# airPi_Controller.net
KiCad netlist of a schematic drawn in Altium Designer
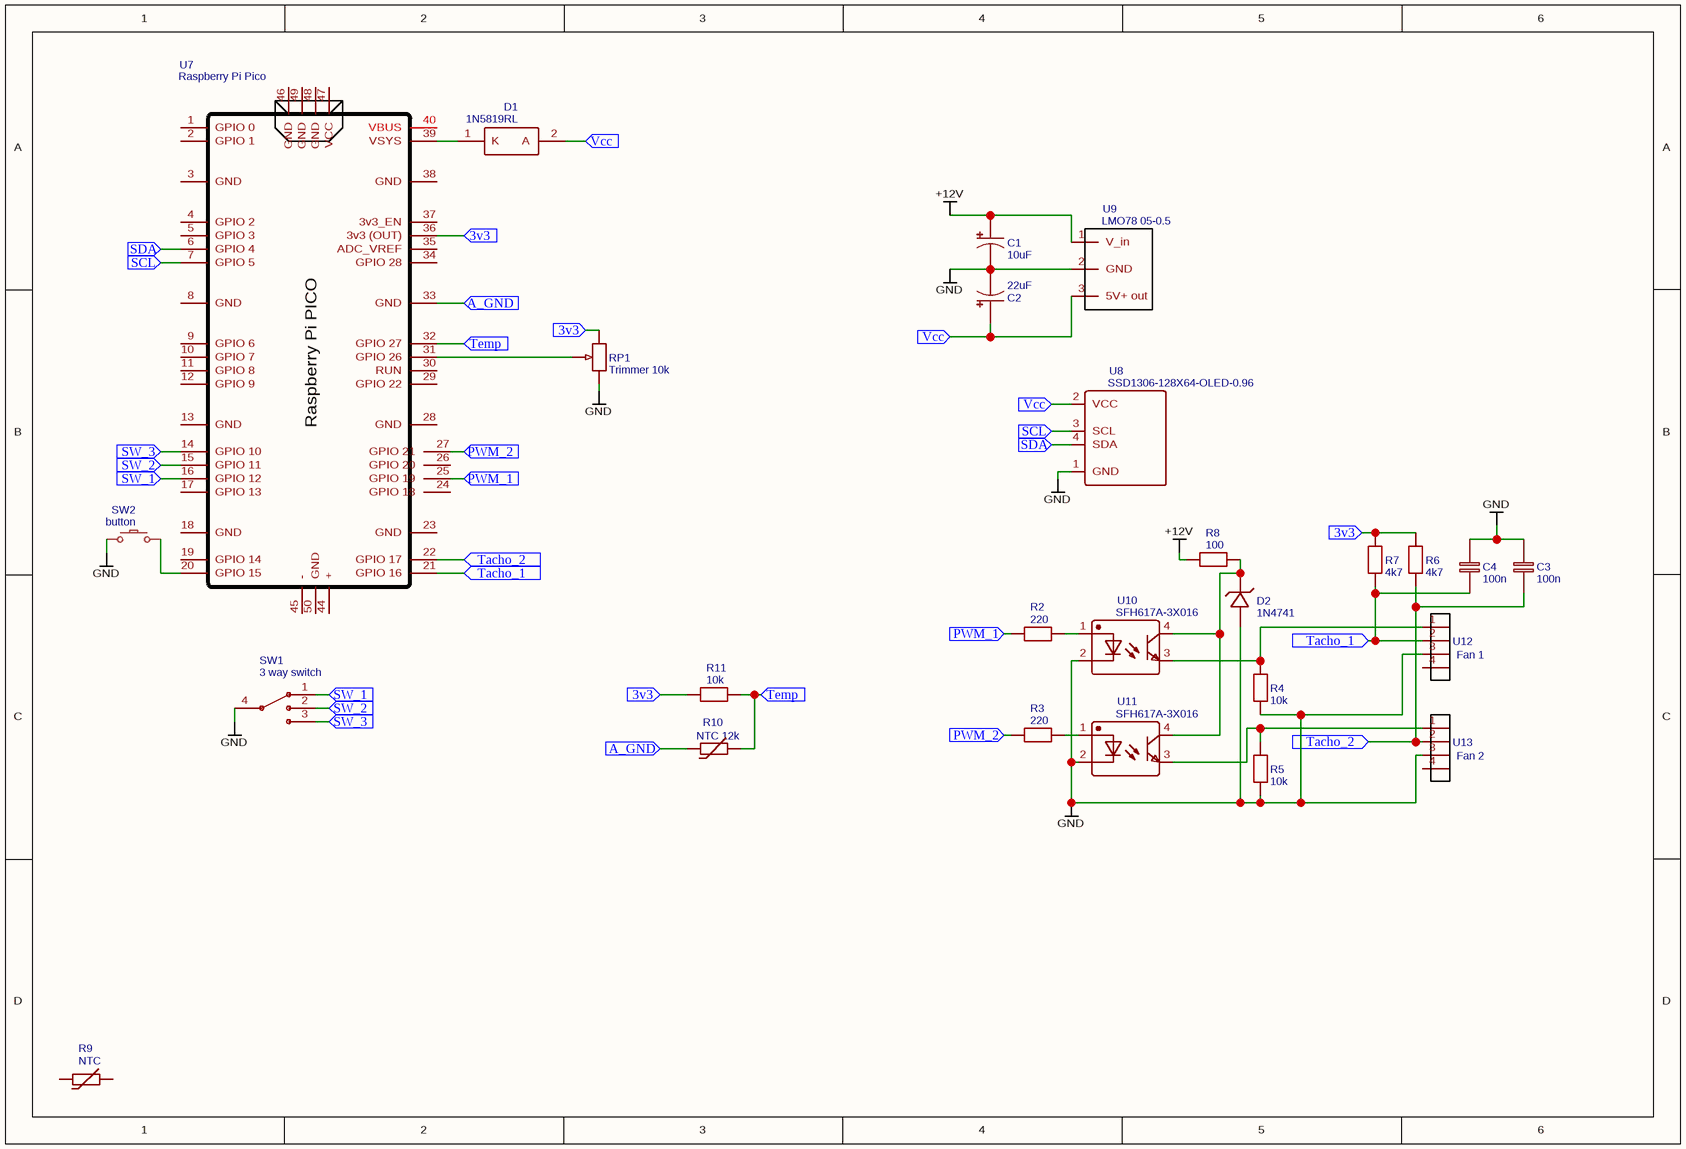
[diagram p0: airPi_Controller.schdoc]

(export (version "E")
  (design (tool "Eeschema 10.0.6"))
  (components
    (comp (ref "C1")
      (value "10uF")
      (fields (field (name "CONTRIBUTOR") "hafiz_8030"))
      (libsource (lib "altium-import") (part "root_0_10uF_"))
    )
    (comp (ref "C2")
      (value "22uF")
      (fields (field (name "CONTRIBUTOR") "hafiz_8030"))
      (libsource (lib "altium-import") (part "root_0_22uF_"))
    )
    (comp (ref "C3")
      (value "100n")
      (fields (field (name "CONTRIBUTOR") "LCEDA_Lib"))
      (libsource (lib "altium-import") (part "root_1_100n_"))
    )
    (comp (ref "C4")
      (value "100n")
      (fields (field (name "CONTRIBUTOR") "LCEDA_Lib"))
      (libsource (lib "altium-import") (part "root_1_100n_"))
    )
    (comp (ref "D1")
      (value "1N5819RL")
      (description "Rectifier, 2-Pin Axial_Lead, Pb-Free, Tape and Reel")
      (libsource (lib "altium-import") (part "root_0_1N5819RL_"))
    )
    (comp (ref "D2")
      (value "1N4741")
      (fields
        (field (name "MANUFACTURER") "onsemi(安森美)")
        (field (name "MANUFACTURER PART") "1N4741A")
        (field (name "CONTRIBUTOR") "LCSC")
      )
      (libsource (lib "altium-import") (part "root_3_1N4741_"))
    )
    (comp (ref "R2")
      (value "220")
      (fields (field (name "CONTRIBUTOR") "LCEDA_Lib"))
      (libsource (lib "altium-import") (part "root_0_220_"))
    )
    (comp (ref "R3")
      (value "220")
      (fields (field (name "CONTRIBUTOR") "LCEDA_Lib"))
      (libsource (lib "altium-import") (part "root_0_220_"))
    )
    (comp (ref "R4")
      (value "10k")
      (fields (field (name "CONTRIBUTOR") "LCEDA_Lib"))
      (libsource (lib "altium-import") (part "root_1_10k_"))
    )
    (comp (ref "R5")
      (value "10k")
      (fields (field (name "CONTRIBUTOR") "LCEDA_Lib"))
      (libsource (lib "altium-import") (part "root_1_10k_"))
    )
    (comp (ref "R6")
      (value "4k7")
      (fields (field (name "CONTRIBUTOR") "LCEDA_Lib"))
      (libsource (lib "altium-import") (part "root_1_4k7_"))
    )
    (comp (ref "R7")
      (value "4k7")
      (fields (field (name "CONTRIBUTOR") "LCEDA_Lib"))
      (libsource (lib "altium-import") (part "root_1_4k7_"))
    )
    (comp (ref "R8")
      (value "100")
      (fields (field (name "CONTRIBUTOR") "LCEDA_Lib"))
      (libsource (lib "altium-import") (part "root_2_100_"))
    )
    (comp (ref "R9")
      (value "NTC")
      (fields (field (name "MANUFACTURER") "RUILON(瑞隆源)") (field (name "MANUFACTURER PART") "NTC 5D-9(弯脚)"))
      (libsource (lib "altium-import") (part "root_0_NTC_"))
    )
    (comp (ref "R10")
      (value "NTC 12k")
      (fields (field (name "MANUFACTURER") "RUILON(瑞隆源)") (field (name "MANUFACTURER PART") "NTC 5D-9(弯脚)"))
      (libsource (lib "altium-import") (part "root_0_NTC 12k_"))
    )
    (comp (ref "R11")
      (value "10k")
      (fields (field (name "CONTRIBUTOR") "LCEDA_Lib"))
      (libsource (lib "altium-import") (part "root_0_10k_"))
    )
    (comp (ref "RP1")
      (value "Trimmer 10k")
      (fields (field (name "CONTRIBUTOR") "LCEDA_Lib"))
      (libsource (lib "altium-import") (part "root_1_Trimmer 10k_"))
    )
    (comp (ref "SW1")
      (value "3 way switch")
      (fields
        (field (name "MANUFACTURER") "ReliaPro")
        (field (name "MANUFACTURER PART") "MSK-11027 Toggle Switches")
        (field (name "CONTRIBUTOR") "ClivePCBDesign")
      )
      (libsource (lib "altium-import") (part "root_0_3 way switch_"))
    )
    (comp (ref "SW2")
      (value "button")
      (fields (field (name "CONTRIBUTOR") "laura.puyet1"))
      (libsource (lib "altium-import") (part "root_0_button_"))
    )
    (comp (ref "U7")
      (value "Raspberry Pi Pico")
      (fields (field (name "CONTRIBUTOR") "grawik"))
      (libsource (lib "altium-import") (part "root_0_Raspberry Pi Pico_"))
    )
    (comp (ref "U8")
      (value "SSD1306-128X64-OLED-0.96")
      (fields (field (name "CONTRIBUTOR") "Think Service"))
      (libsource (lib "altium-import") (part "root_0_SSD1306-128X64-OLED-0.96_"))
    )
    (comp (ref "U9")
      (value "LMO78 05-0.5")
      (fields (field (name "CONTRIBUTOR") "Martin Heiter"))
      (libsource (lib "altium-import") (part "root_3_LMO78 05-0.5_"))
    )
    (comp (ref "U10")
      (value "SFH617A-3X016")
      (fields (field (name "MANUFACTURER") "VISHAY(威世)") (field (name "CONTRIBUTOR") "lcsc"))
      (libsource (lib "altium-import") (part "root_0_SFH617A-3X016_"))
    )
    (comp (ref "U11")
      (value "SFH617A-3X016")
      (fields (field (name "MANUFACTURER") "VISHAY(威世)") (field (name "CONTRIBUTOR") "lcsc"))
      (libsource (lib "altium-import") (part "root_0_SFH617A-3X016_"))
    )
    (comp (ref "U12")
      (value "Fan 1")
      (fields (field (name "CONTRIBUTOR") "s1atbewie.de"))
      (libsource (lib "altium-import") (part "root_0_Fan 1_"))
    )
    (comp (ref "U13")
      (value "Fan 2")
      (fields (field (name "CONTRIBUTOR") "s1atbewie.de"))
      (libsource (lib "altium-import") (part "root_0_Fan 2_"))
    )
  )
  (nets
    (net (code "1") (name "+12V") (class "Default")
      (node (ref "C1") (pin "1") (pinfunction "1_1") (pintype "passive"))
      (node (ref "R8") (pin "2") (pinfunction "2_2") (pintype "passive"))
      (node (ref "U9") (pin "1") (pinfunction "V_in_1") (pintype "passive"))
    )
    (net (code "2") (name "/3v3") (class "Default")
      (node (ref "R11") (pin "1") (pinfunction "1_1") (pintype "passive"))
      (node (ref "R6") (pin "2") (pinfunction "2_2") (pintype "passive"))
      (node (ref "R7") (pin "2") (pinfunction "2_2") (pintype "passive"))
      (node (ref "RP1") (pin "3") (pinfunction "3_3") (pintype "passive"))
      (node (ref "U7") (pin "36") (pinfunction "3v3_(OUT)_36") (pintype "passive"))
    )
    (net (code "3") (name "/A_GND") (class "Default")
      (node (ref "R10") (pin "1") (pinfunction "1_1") (pintype "passive"))
      (node (ref "U7") (pin "33") (pinfunction "GND_33") (pintype "passive"))
    )
    (net (code "4") (name "/PWM_1") (class "Default")
      (node (ref "R2") (pin "1") (pinfunction "1_1") (pintype "passive"))
      (node (ref "U7") (pin "25") (pinfunction "GPIO_19_25") (pintype "passive"))
    )
    (net (code "5") (name "/PWM_2") (class "Default")
      (node (ref "R3") (pin "1") (pinfunction "1_1") (pintype "passive"))
      (node (ref "U7") (pin "27") (pinfunction "GPIO_21_27") (pintype "passive"))
    )
    (net (code "6") (name "/SCL") (class "Default")
      (node (ref "U7") (pin "7") (pinfunction "GPIO_5_7") (pintype "passive"))
      (node (ref "U8") (pin "3") (pinfunction "SCL_3") (pintype "passive"))
    )
    (net (code "7") (name "/SDA") (class "Default")
      (node (ref "U7") (pin "6") (pinfunction "GPIO_4_6") (pintype "passive"))
      (node (ref "U8") (pin "4") (pinfunction "SDA_4") (pintype "passive"))
    )
    (net (code "8") (name "/SW_1") (class "Default")
      (node (ref "SW1") (pin "1") (pinfunction "1_1") (pintype "passive"))
      (node (ref "U7") (pin "16") (pinfunction "GPIO_12_16") (pintype "passive"))
    )
    (net (code "9") (name "/SW_2") (class "Default")
      (node (ref "SW1") (pin "2") (pinfunction "3_2") (pintype "passive"))
      (node (ref "U7") (pin "15") (pinfunction "GPIO_11_15") (pintype "passive"))
    )
    (net (code "10") (name "/SW_3") (class "Default")
      (node (ref "SW1") (pin "3") (pinfunction "4_3") (pintype "passive"))
      (node (ref "U7") (pin "14") (pinfunction "GPIO_10_14") (pintype "passive"))
    )
    (net (code "11") (name "/Tacho_1") (class "Default")
      (node (ref "C4") (pin "1") (pinfunction "1_1") (pintype "passive"))
      (node (ref "R7") (pin "1") (pinfunction "1_1") (pintype "passive"))
      (node (ref "U12") (pin "2") (pinfunction "2_2") (pintype "passive"))
      (node (ref "U7") (pin "21") (pinfunction "GPIO_16_21") (pintype "passive"))
    )
    (net (code "12") (name "/Tacho_2") (class "Default")
      (node (ref "C3") (pin "1") (pinfunction "1_1") (pintype "passive"))
      (node (ref "R6") (pin "1") (pinfunction "1_1") (pintype "passive"))
      (node (ref "U13") (pin "2") (pinfunction "2_2") (pintype "passive"))
      (node (ref "U7") (pin "22") (pinfunction "GPIO_17_22") (pintype "passive"))
    )
    (net (code "13") (name "/Temp") (class "Default")
      (node (ref "R10") (pin "2") (pinfunction "2_2") (pintype "passive"))
      (node (ref "R11") (pin "2") (pinfunction "2_2") (pintype "passive"))
      (node (ref "U7") (pin "32") (pinfunction "GPIO_27_32") (pintype "passive"))
    )
    (net (code "14") (name "/Vcc") (class "Default")
      (node (ref "C2") (pin "1") (pinfunction "1_1") (pintype "passive"))
      (node (ref "D1") (pin "2") (pinfunction "A_2") (pintype "passive"))
      (node (ref "U8") (pin "2") (pinfunction "VCC_2") (pintype "passive"))
      (node (ref "U9") (pin "3") (pinfunction "5V+_out_3") (pintype "passive"))
    )
    (net (code "15") (name "GND") (class "Default")
      (node (ref "C1") (pin "2") (pinfunction "2_2") (pintype "passive"))
      (node (ref "C2") (pin "2") (pinfunction "2_2") (pintype "passive"))
      (node (ref "C3") (pin "2") (pinfunction "2_2") (pintype "passive"))
      (node (ref "C4") (pin "2") (pinfunction "2_2") (pintype "passive"))
      (node (ref "D2") (pin "2") (pinfunction "A_2") (pintype "passive"))
      (node (ref "R4") (pin "1") (pinfunction "1_1") (pintype "passive"))
      (node (ref "R5") (pin "1") (pinfunction "1_1") (pintype "passive"))
      (node (ref "RP1") (pin "1") (pinfunction "1_1") (pintype "passive"))
      (node (ref "SW1") (pin "4") (pinfunction "2_4") (pintype "passive"))
      (node (ref "SW2") (pin "P$ACTIVE") (pinfunction "P$ACTIVE_P$ACTIVE") (pintype "passive"))
      (node (ref "U10") (pin "2") (pinfunction "C_2") (pintype "passive"))
      (node (ref "U11") (pin "2") (pinfunction "C_2") (pintype "passive"))
      (node (ref "U12") (pin "3") (pinfunction "3_3") (pintype "passive"))
      (node (ref "U13") (pin "3") (pinfunction "3_3") (pintype "passive"))
      (node (ref "U8") (pin "1") (pinfunction "GND_1") (pintype "passive"))
      (node (ref "U9") (pin "2") (pinfunction "GND_2") (pintype "passive"))
    )
    (net (code "16") (name "Net-(D1-K)") (class "Default")
      (node (ref "D1") (pin "1") (pinfunction "K_1") (pintype "passive"))
      (node (ref "U7") (pin "39") (pinfunction "VSYS_39") (pintype "passive"))
    )
    (net (code "17") (name "Net-(D2-K)") (class "Default")
      (node (ref "D2") (pin "1") (pinfunction "K_1") (pintype "passive"))
      (node (ref "R8") (pin "1") (pinfunction "1_1") (pintype "passive"))
      (node (ref "U10") (pin "4") (pinfunction "C_4") (pintype "passive"))
      (node (ref "U11") (pin "4") (pinfunction "C_4") (pintype "passive"))
    )
    (net (code "18") (name "Net-(U7-GPIO_15)") (class "Default")
      (node (ref "SW2") (pin "P$GND") (pinfunction "P$GND_P$GND") (pintype "passive"))
      (node (ref "U7") (pin "20") (pinfunction "GPIO_15_20") (pintype "passive"))
    )
    (net (code "19") (name "Net-(U7-GPIO_26)") (class "Default")
      (node (ref "RP1") (pin "2") (pinfunction "2_2") (pintype "passive"))
      (node (ref "U7") (pin "31") (pinfunction "GPIO_26_31") (pintype "passive"))
    )
    (net (code "20") (name "Net-(U10-A)") (class "Default")
      (node (ref "R2") (pin "2") (pinfunction "2_2") (pintype "passive"))
      (node (ref "U10") (pin "1") (pinfunction "A_1") (pintype "passive"))
    )
    (net (code "21") (name "Net-(U10-E)") (class "Default")
      (node (ref "R4") (pin "2") (pinfunction "2_2") (pintype "passive"))
      (node (ref "U10") (pin "3") (pinfunction "E_3") (pintype "passive"))
      (node (ref "U12") (pin "1") (pinfunction "1_1") (pintype "passive"))
    )
    (net (code "22") (name "Net-(U11-A)") (class "Default")
      (node (ref "R3") (pin "2") (pinfunction "2_2") (pintype "passive"))
      (node (ref "U11") (pin "1") (pinfunction "A_1") (pintype "passive"))
    )
    (net (code "23") (name "Net-(U11-E)") (class "Default")
      (node (ref "R5") (pin "2") (pinfunction "2_2") (pintype "passive"))
      (node (ref "U11") (pin "3") (pinfunction "E_3") (pintype "passive"))
      (node (ref "U13") (pin "1") (pinfunction "1_1") (pintype "passive"))
    )
    (net (code "24") (name "unconnected-(R9-Pad1)") (class "Default")
      (node (ref "R9") (pin "1") (pinfunction "1_1") (pintype "passive"))
    )
    (net (code "25") (name "unconnected-(R9-Pad2)") (class "Default")
      (node (ref "R9") (pin "2") (pinfunction "2_2") (pintype "passive"))
    )
    (net (code "26") (name "unconnected-(U7-+-Pad44)") (class "Default")
      (node (ref "U7") (pin "44") (pinfunction "+_44") (pintype "passive"))
    )
    (net (code "27") (name "unconnected-(U7---Pad45)") (class "Default")
      (node (ref "U7") (pin "45") (pinfunction "-_45") (pintype "passive"))
    )
    (net (code "28") (name "unconnected-(U7-3v3_EN-Pad37)") (class "Default")
      (node (ref "U7") (pin "37") (pinfunction "3v3_EN_37") (pintype "passive"))
    )
    (net (code "29") (name "unconnected-(U7-ADC_VREF-Pad35)") (class "Default")
      (node (ref "U7") (pin "35") (pinfunction "ADC_VREF_35") (pintype "passive"))
    )
    (net (code "30") (name "unconnected-(U7-GND-Pad3)") (class "Default")
      (node (ref "U7") (pin "3") (pinfunction "GND_3") (pintype "passive"))
    )
    (net (code "31") (name "unconnected-(U7-GND-Pad8)") (class "Default")
      (node (ref "U7") (pin "8") (pinfunction "GND_8") (pintype "passive"))
    )
    (net (code "32") (name "unconnected-(U7-GND-Pad13)") (class "Default")
      (node (ref "U7") (pin "13") (pinfunction "GND_13") (pintype "passive"))
    )
    (net (code "33") (name "unconnected-(U7-GND-Pad18)") (class "Default")
      (node (ref "U7") (pin "18") (pinfunction "GND_18") (pintype "passive"))
    )
    (net (code "34") (name "unconnected-(U7-GND-Pad23)") (class "Default")
      (node (ref "U7") (pin "23") (pinfunction "GND_23") (pintype "passive"))
    )
    (net (code "35") (name "unconnected-(U7-GND-Pad28)") (class "Default")
      (node (ref "U7") (pin "28") (pinfunction "GND_28") (pintype "passive"))
    )
    (net (code "36") (name "unconnected-(U7-GND-Pad38)") (class "Default")
      (node (ref "U7") (pin "38") (pinfunction "GND_38") (pintype "passive"))
    )
    (net (code "37") (name "unconnected-(U7-GND-Pad46)") (class "Default")
      (node (ref "U7") (pin "46") (pinfunction "GND_46") (pintype "passive"))
    )
    (net (code "38") (name "unconnected-(U7-GND-Pad48)") (class "Default")
      (node (ref "U7") (pin "48") (pinfunction "GND_48") (pintype "passive"))
    )
    (net (code "39") (name "unconnected-(U7-GND-Pad49)") (class "Default")
      (node (ref "U7") (pin "49") (pinfunction "GND_49") (pintype "passive"))
    )
    (net (code "40") (name "unconnected-(U7-GND-Pad50)") (class "Default")
      (node (ref "U7") (pin "50") (pinfunction "GND_50") (pintype "passive"))
    )
    (net (code "41") (name "unconnected-(U7-GPIO_0-Pad1)") (class "Default")
      (node (ref "U7") (pin "1") (pinfunction "GPIO_0_1") (pintype "passive"))
    )
    (net (code "42") (name "unconnected-(U7-GPIO_1-Pad2)") (class "Default")
      (node (ref "U7") (pin "2") (pinfunction "GPIO_1_2") (pintype "passive"))
    )
    (net (code "43") (name "unconnected-(U7-GPIO_2-Pad4)") (class "Default")
      (node (ref "U7") (pin "4") (pinfunction "GPIO_2_4") (pintype "passive"))
    )
    (net (code "44") (name "unconnected-(U7-GPIO_3-Pad5)") (class "Default")
      (node (ref "U7") (pin "5") (pinfunction "GPIO_3_5") (pintype "passive"))
    )
    (net (code "45") (name "unconnected-(U7-GPIO_6-Pad9)") (class "Default")
      (node (ref "U7") (pin "9") (pinfunction "GPIO_6_9") (pintype "passive"))
    )
    (net (code "46") (name "unconnected-(U7-GPIO_7-Pad10)") (class "Default")
      (node (ref "U7") (pin "10") (pinfunction "GPIO_7_10") (pintype "passive"))
    )
    (net (code "47") (name "unconnected-(U7-GPIO_8-Pad11)") (class "Default")
      (node (ref "U7") (pin "11") (pinfunction "GPIO_8_11") (pintype "passive"))
    )
    (net (code "48") (name "unconnected-(U7-GPIO_9-Pad12)") (class "Default")
      (node (ref "U7") (pin "12") (pinfunction "GPIO_9_12") (pintype "passive"))
    )
    (net (code "49") (name "unconnected-(U7-GPIO_13-Pad17)") (class "Default")
      (node (ref "U7") (pin "17") (pinfunction "GPIO_13_17") (pintype "passive"))
    )
    (net (code "50") (name "unconnected-(U7-GPIO_14-Pad19)") (class "Default")
      (node (ref "U7") (pin "19") (pinfunction "GPIO_14_19") (pintype "passive"))
    )
    (net (code "51") (name "unconnected-(U7-GPIO_18-Pad24)") (class "Default")
      (node (ref "U7") (pin "24") (pinfunction "GPIO_18_24") (pintype "passive"))
    )
    (net (code "52") (name "unconnected-(U7-GPIO_20-Pad26)") (class "Default")
      (node (ref "U7") (pin "26") (pinfunction "GPIO_20_26") (pintype "passive"))
    )
    (net (code "53") (name "unconnected-(U7-GPIO_22-Pad29)") (class "Default")
      (node (ref "U7") (pin "29") (pinfunction "GPIO_22_29") (pintype "passive"))
    )
    (net (code "54") (name "unconnected-(U7-GPIO_28-Pad34)") (class "Default")
      (node (ref "U7") (pin "34") (pinfunction "GPIO_28_34") (pintype "passive"))
    )
    (net (code "55") (name "unconnected-(U7-RUN-Pad30)") (class "Default")
      (node (ref "U7") (pin "30") (pinfunction "RUN_30") (pintype "passive"))
    )
    (net (code "56") (name "unconnected-(U7-VBUS-Pad40)") (class "Default")
      (node (ref "U7") (pin "40") (pinfunction "VBUS_40") (pintype "passive"))
    )
    (net (code "57") (name "unconnected-(U7-VCC-Pad47)") (class "Default")
      (node (ref "U7") (pin "47") (pinfunction "VCC_47") (pintype "passive"))
    )
    (net (code "58") (name "unconnected-(U12-Pad4)") (class "Default")
      (node (ref "U12") (pin "4") (pinfunction "4_4") (pintype "passive"))
    )
    (net (code "59") (name "unconnected-(U13-Pad4)") (class "Default")
      (node (ref "U13") (pin "4") (pinfunction "4_4") (pintype "passive"))
    )
  )
)
